# ESD_Protection.net
KiCad netlist of a schematic drawn in Altium Designer
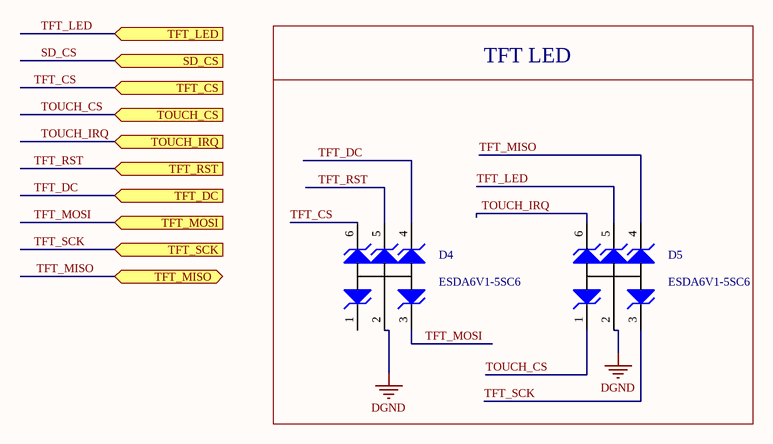
[diagram p0: ESD_Protection.SchDoc]

(export (version "E")
  (design (tool "Eeschema 10.0.6"))
  (components
    (comp (ref "D4")
      (value "ESDA6V1-5SC6")
      (footprint "MF06A_N")
      (description "ESDA Series 5 Channel 6.1 V 50 pF SMT Uni Directional Transil Array - SOT-23-6L")
      (libsource (lib "CommunityVault") (part "CMP-924f5b40f9684d88-1"))
    )
    (comp (ref "D5")
      (value "ESDA6V1-5SC6")
      (footprint "MF06A_N")
      (description "ESDA Series 5 Channel 6.1 V 50 pF SMT Uni Directional Transil Array - SOT-23-6L")
      (libsource (lib "CommunityVault") (part "CMP-924f5b40f9684d88-1"))
    )
  )
  (nets
    (net (code "2") (name "/TFT_CS") (class "Default")
      (node (ref "D4") (pin "6") (pinfunction "A_6") (pintype "passive"))
    )
    (net (code "3") (name "/TFT_DC") (class "Default")
      (node (ref "D4") (pin "4") (pinfunction "A_4") (pintype "passive"))
    )
    (net (code "4") (name "/TFT_LED") (class "Default")
      (node (ref "D5") (pin "5") (pinfunction "A_5") (pintype "passive"))
    )
    (net (code "5") (name "/TFT_MISO") (class "Default")
      (node (ref "D5") (pin "4") (pinfunction "A_4") (pintype "passive"))
    )
    (net (code "6") (name "/TFT_MOSI") (class "Default")
      (node (ref "D4") (pin "3") (pinfunction "K_3") (pintype "passive"))
    )
    (net (code "7") (name "/TFT_RST") (class "Default")
      (node (ref "D4") (pin "5") (pinfunction "A_5") (pintype "passive"))
    )
    (net (code "8") (name "/TFT_SCK") (class "Default")
      (node (ref "D5") (pin "3") (pinfunction "K_3") (pintype "passive"))
    )
    (net (code "9") (name "/TOUCH_CS") (class "Default")
      (node (ref "D5") (pin "1") (pinfunction "K_1") (pintype "passive"))
    )
    (net (code "10") (name "/TOUCH_IRQ") (class "Default")
      (node (ref "D5") (pin "6") (pinfunction "A_6") (pintype "passive"))
    )
    (net (code "11") (name "DGND") (class "Default")
      (node (ref "D4") (pin "2") (pinfunction "K_2") (pintype "passive"))
      (node (ref "D5") (pin "2") (pinfunction "K_2") (pintype "passive"))
    )
    (net (code "12") (name "unconnected-(D4-K-Pad1)") (class "Default")
      (node (ref "D4") (pin "1") (pinfunction "K_1") (pintype "passive"))
    )
  )
)
